# passive_RC_high_pass_filter.net
KiCad netlist of a schematic drawn in EAGLE
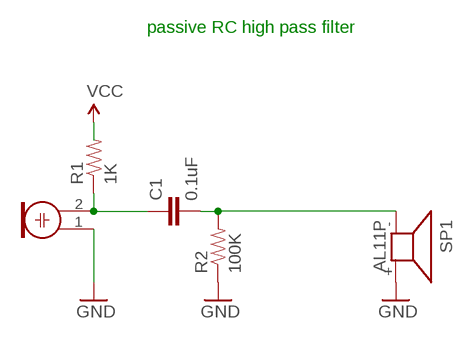
[diagram p0: schematic, sheet 1]

(export (version "E")
  (design (tool "Eeschema 10.0.6"))
  (components
    (comp (ref "C1")
      (value "0.1uF")
      (footprint "eagle-import:CAP-PTH-SMALL2")
      (libsource (lib "eagle-import") (part "CAPPTH2"))
    )
    (comp (ref "M1")
      (value "ELECTRET_MICROPHON-F6050AP")
      (footprint "eagle-import:F6050AP")
      (libsource (lib "eagle-import") (part "ELECTRET_MICROPHON-F6050AP"))
    )
    (comp (ref "R1")
      (value "1K")
      (footprint "eagle-import:AXIAL-0.3")
      (libsource (lib "eagle-import") (part "RESISTORAXIAL-0.3"))
    )
    (comp (ref "R2")
      (value "100K")
      (footprint "eagle-import:AXIAL-0.3")
      (libsource (lib "eagle-import") (part "RESISTORAXIAL-0.3"))
    )
    (comp (ref "SP1")
      (value "AL11P")
      (footprint "eagle-import:AL11P")
      (libsource (lib "eagle-import") (part "AL11P"))
    )
  )
  (nets
    (net (code "1") (name "GND") (class "Default")
      (node (ref "M1") (pin "1") (pinfunction "1_1") (pintype "passive"))
      (node (ref "R2") (pin "P$1") (pinfunction "1_P$1") (pintype "passive"))
      (node (ref "SP1") (pin "+") (pinfunction "2_+") (pintype "passive"))
    )
    (net (code "2") (name "Net-(R1-1)") (class "Default")
      (node (ref "C1") (pin "1") (pinfunction "1_1") (pintype "passive"))
      (node (ref "M1") (pin "2") (pinfunction "2_2") (pintype "passive"))
      (node (ref "R1") (pin "P$1") (pinfunction "1_P$1") (pintype "passive"))
    )
    (net (code "3") (name "Net-(R2-2)") (class "Default")
      (node (ref "C1") (pin "2") (pinfunction "2_2") (pintype "passive"))
      (node (ref "R2") (pin "P$2") (pinfunction "2_P$2") (pintype "passive"))
      (node (ref "SP1") (pin "-") (pinfunction "1_-") (pintype "passive"))
    )
    (net (code "4") (name "VCC") (class "Default")
      (node (ref "R1") (pin "P$2") (pinfunction "2_P$2") (pintype "passive"))
    )
  )
)
